# rcx_hack_v2.net
KiCad netlist of a schematic drawn in EAGLE
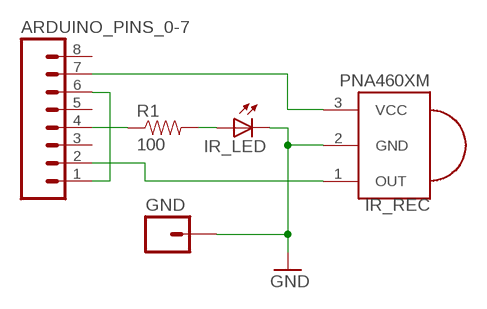
[diagram p0: schematic, sheet 1]

(export (version "E")
  (design (tool "Eeschema 10.0.6"))
  (components
    (comp (ref "ARDUINO_PINS_0-7")
      (value "M08LOCK")
      (footprint "eagle-import:1X08_LOCK")
      (libsource (lib "eagle-import") (part "M08LOCK"))
    )
    (comp (ref "GND")
      (value "M01PTH_LONGPAD")
      (footprint "eagle-import:1X01_LONGPAD")
      (libsource (lib "eagle-import") (part "M01PTH_LONGPAD"))
    )
    (comp (ref "IR_LED")
      (value "LED5MM")
      (footprint "eagle-import:LED5MM")
      (libsource (lib "eagle-import") (part "LED5MM"))
    )
    (comp (ref "IR_REC")
      (value "PNA460XM")
      (footprint "eagle-import:PNA460XM")
      (libsource (lib "eagle-import") (part "PNA460XM"))
    )
    (comp (ref "R1")
      (value "100")
      (footprint "eagle-import:AXIAL-0.3")
      (libsource (lib "eagle-import") (part "RESISTORAXIAL-0.3"))
    )
  )
  (nets
    (net (code "1") (name "GND") (class "Default")
      (node (ref "GND") (pin "1") (pinfunction "1_1") (pintype "passive"))
      (node (ref "IR_LED") (pin "K") (pinfunction "C_K") (pintype "passive"))
      (node (ref "IR_REC") (pin "2") (pinfunction "GND_2") (pintype "power_in"))
    )
    (net (code "2") (name "Net-(ARDUINO_PINS_0-7-Pad1)") (class "Default")
      (node (ref "ARDUINO_PINS_0-7") (pin "1") (pinfunction "1_1") (pintype "passive"))
      (node (ref "ARDUINO_PINS_0-7") (pin "6") (pinfunction "6_6") (pintype "passive"))
    )
    (net (code "3") (name "Net-(IR_REC-OUT)") (class "Default")
      (node (ref "ARDUINO_PINS_0-7") (pin "2") (pinfunction "2_2") (pintype "passive"))
      (node (ref "IR_REC") (pin "1") (pinfunction "OUT_1") (pintype "output"))
    )
    (net (code "4") (name "Net-(IR_REC-VCC)") (class "Default")
      (node (ref "ARDUINO_PINS_0-7") (pin "7") (pinfunction "7_7") (pintype "passive"))
      (node (ref "IR_REC") (pin "3") (pinfunction "VCC_3") (pintype "power_in"))
    )
    (net (code "5") (name "Net-(R1-1)") (class "Default")
      (node (ref "ARDUINO_PINS_0-7") (pin "4") (pinfunction "4_4") (pintype "passive"))
      (node (ref "R1") (pin "P$1") (pinfunction "1_P$1") (pintype "passive"))
    )
    (net (code "6") (name "Net-(R1-2)") (class "Default")
      (node (ref "IR_LED") (pin "A") (pinfunction "A_A") (pintype "passive"))
      (node (ref "R1") (pin "P$2") (pinfunction "2_P$2") (pintype "passive"))
    )
    (net (code "7") (name "unconnected-(ARDUINO_PINS_0-7-Pad3)") (class "Default")
      (node (ref "ARDUINO_PINS_0-7") (pin "3") (pinfunction "3_3") (pintype "passive"))
    )
    (net (code "8") (name "unconnected-(ARDUINO_PINS_0-7-Pad5)") (class "Default")
      (node (ref "ARDUINO_PINS_0-7") (pin "5") (pinfunction "5_5") (pintype "passive"))
    )
    (net (code "9") (name "unconnected-(ARDUINO_PINS_0-7-Pad8)") (class "Default")
      (node (ref "ARDUINO_PINS_0-7") (pin "8") (pinfunction "8_8") (pintype "passive"))
    )
  )
)
